# 1tm32_test.net
KiCad netlist of a schematic drawn in EAGLE
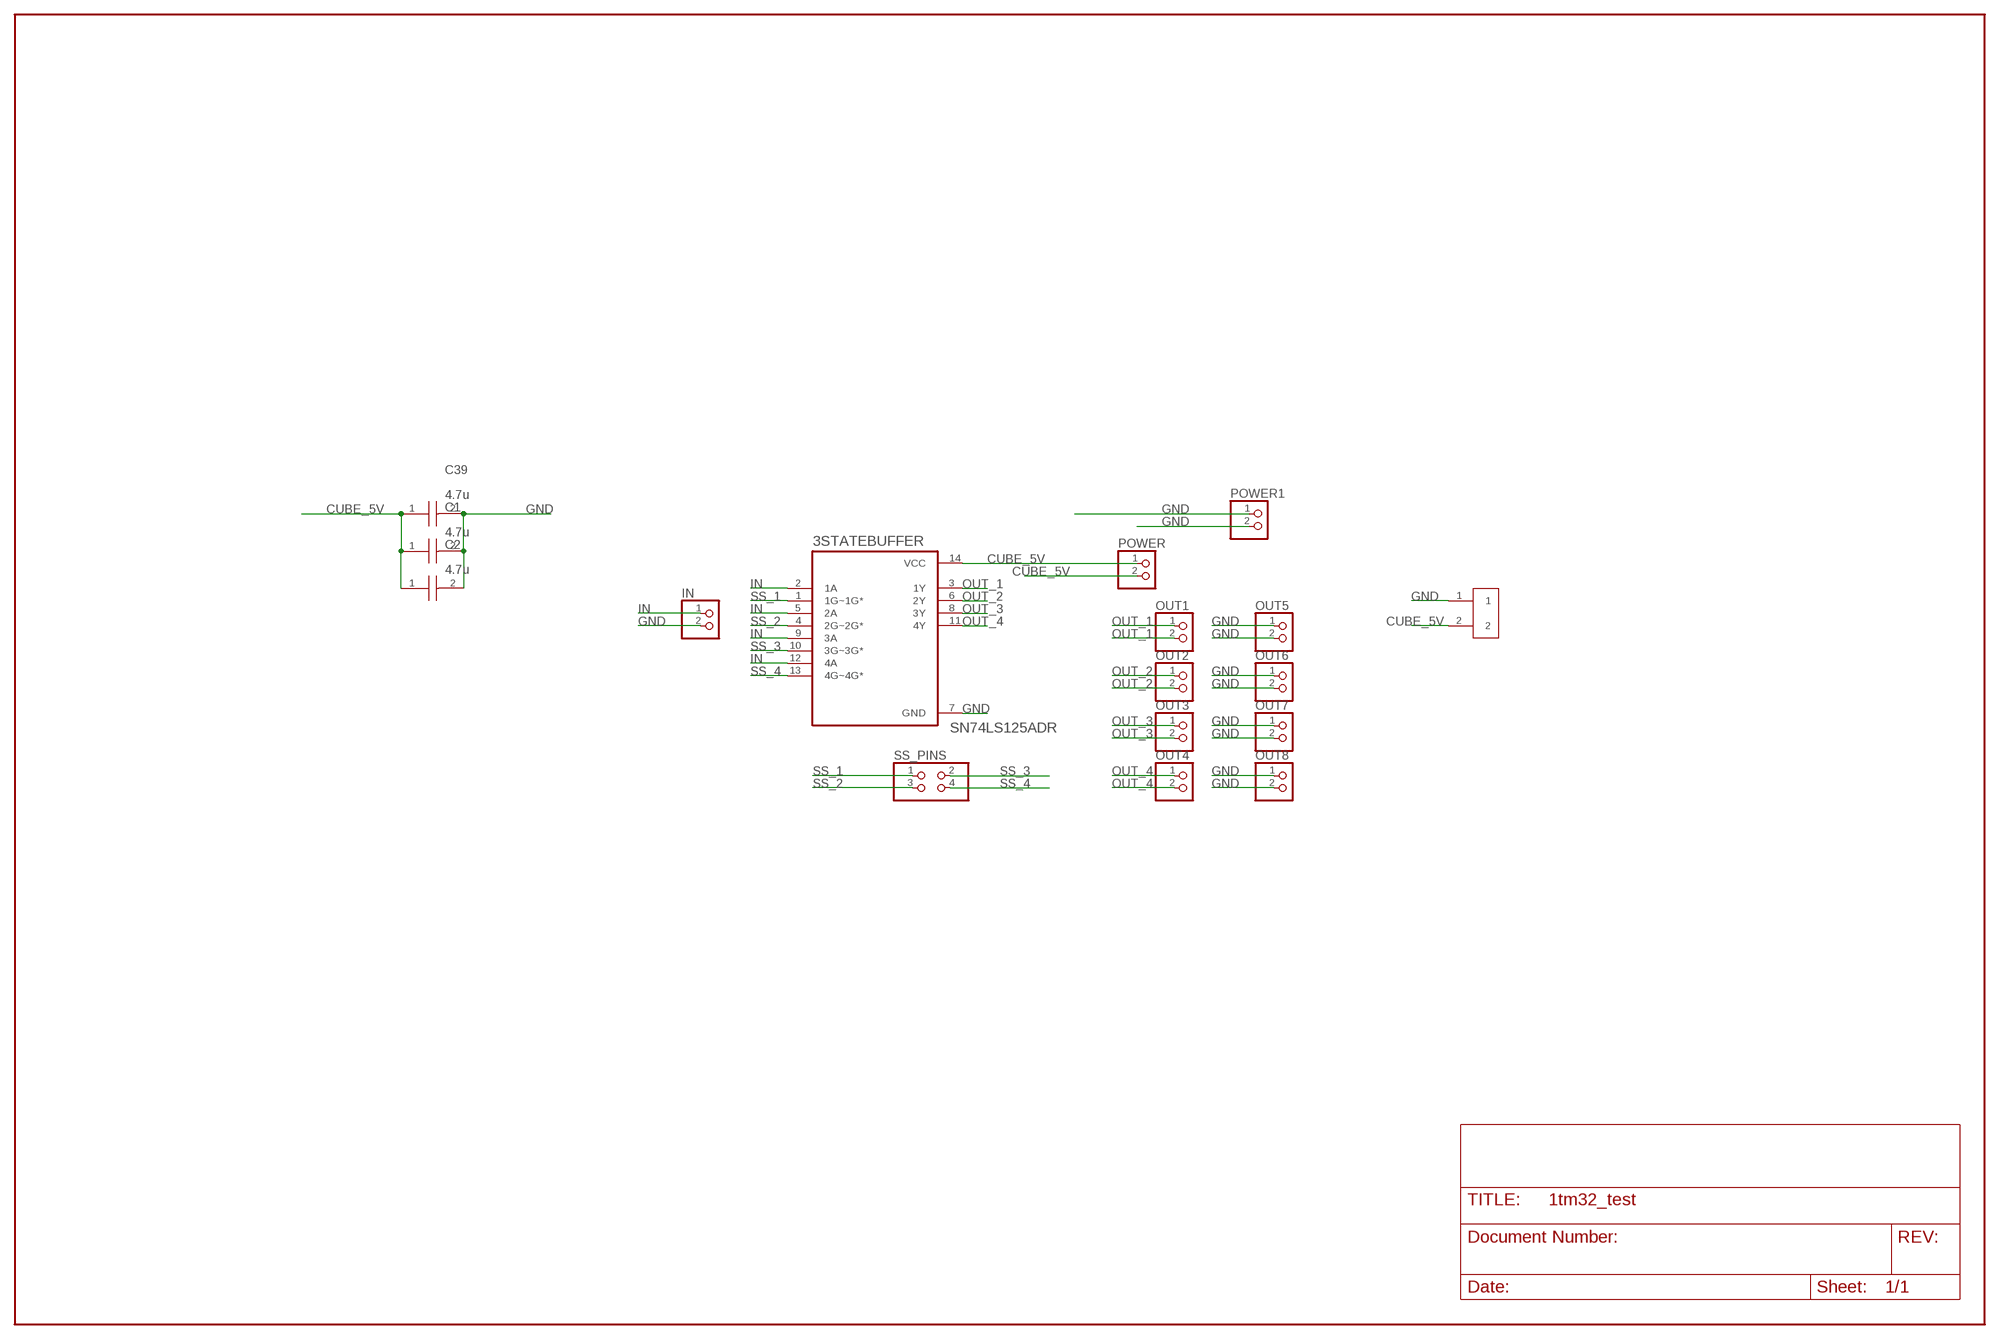
[diagram p0: schematic, sheet 1]

(export (version "E")
  (design (tool "Eeschema 10.0.6"))
  (components
    (comp (ref "3STATEBUFFER")
      (value "SN74LS125ADR")
      (footprint "eagle-import:SOIC127P600X175-14N")
      (fields (field (name "MF") "Texas Instruments"))
      (libsource (lib "eagle-import") (part "SN74LS125ADR"))
    )
    (comp (ref "C1")
      (value "4.7u")
      (footprint "eagle-import:CAPC2012X145N")
      (fields
        (field (name "MANUFACTURER_PART_NUMBER") "GRT21BC71H475KE13L")
        (field (name "MOUSER_PART_NUMBER") "81-GRT21BC71H475KE3L")
      )
      (libsource (lib "eagle-import") (part "GRT21BC71H475KE13L"))
    )
    (comp (ref "C2")
      (value "4.7u")
      (footprint "eagle-import:CAPC2012X145N")
      (fields
        (field (name "MANUFACTURER_PART_NUMBER") "GRT21BC71H475KE13L")
        (field (name "MOUSER_PART_NUMBER") "81-GRT21BC71H475KE3L")
      )
      (libsource (lib "eagle-import") (part "GRT21BC71H475KE13L"))
    )
    (comp (ref "C39")
      (value "4.7u")
      (footprint "eagle-import:CAPC2012X145N")
      (fields
        (field (name "MANUFACTURER_PART_NUMBER") "GRT21BC71H475KE13L")
        (field (name "MOUSER_PART_NUMBER") "81-GRT21BC71H475KE3L")
      )
      (libsource (lib "eagle-import") (part "GRT21BC71H475KE13L"))
    )
    (comp (ref "IN")
      (value "PINHD-1X2")
      (footprint "eagle-import:1X02")
      (libsource (lib "eagle-import") (part "PINHD-1X2"))
    )
    (comp (ref "J1")
      (value "1935161")
      (footprint "eagle-import:PHOENIX_1935161")
      (fields (field (name "MF") "Phoenix Contact"))
      (libsource (lib "eagle-import") (part "1935161"))
    )
    (comp (ref "OUT1")
      (value "PINHD-1X2")
      (footprint "eagle-import:1X02")
      (libsource (lib "eagle-import") (part "PINHD-1X2"))
    )
    (comp (ref "OUT2")
      (value "PINHD-1X2")
      (footprint "eagle-import:1X02")
      (libsource (lib "eagle-import") (part "PINHD-1X2"))
    )
    (comp (ref "OUT3")
      (value "PINHD-1X2")
      (footprint "eagle-import:1X02")
      (libsource (lib "eagle-import") (part "PINHD-1X2"))
    )
    (comp (ref "OUT4")
      (value "PINHD-1X2")
      (footprint "eagle-import:1X02")
      (libsource (lib "eagle-import") (part "PINHD-1X2"))
    )
    (comp (ref "OUT5")
      (value "PINHD-1X2")
      (footprint "eagle-import:1X02")
      (libsource (lib "eagle-import") (part "PINHD-1X2"))
    )
    (comp (ref "OUT6")
      (value "PINHD-1X2")
      (footprint "eagle-import:1X02")
      (libsource (lib "eagle-import") (part "PINHD-1X2"))
    )
    (comp (ref "OUT7")
      (value "PINHD-1X2")
      (footprint "eagle-import:1X02")
      (libsource (lib "eagle-import") (part "PINHD-1X2"))
    )
    (comp (ref "OUT8")
      (value "PINHD-1X2")
      (footprint "eagle-import:1X02")
      (libsource (lib "eagle-import") (part "PINHD-1X2"))
    )
    (comp (ref "POWER")
      (value "PINHD-1X2")
      (footprint "eagle-import:1X02")
      (libsource (lib "eagle-import") (part "PINHD-1X2"))
    )
    (comp (ref "POWER1")
      (value "PINHD-1X2")
      (footprint "eagle-import:1X02")
      (libsource (lib "eagle-import") (part "PINHD-1X2"))
    )
    (comp (ref "SS_PINS")
      (value "PINHD-2X2")
      (footprint "eagle-import:2X02")
      (libsource (lib "eagle-import") (part "PINHD-2X2"))
    )
  )
  (nets
    (net (code "1") (name "/CUBE_5V") (class "Default")
      (node (ref "3STATEBUFFER") (pin "14") (pinfunction "VCC_14") (pintype "power_in"))
      (node (ref "C1") (pin "1") (pinfunction "1_1") (pintype "bidirectional"))
      (node (ref "C2") (pin "1") (pinfunction "1_1") (pintype "bidirectional"))
      (node (ref "C39") (pin "1") (pinfunction "1_1") (pintype "bidirectional"))
      (node (ref "J1") (pin "2") (pinfunction "2_2") (pintype "passive"))
      (node (ref "POWER") (pin "1") (pinfunction "1_1") (pintype "passive"))
      (node (ref "POWER") (pin "2") (pinfunction "2_2") (pintype "passive"))
    )
    (net (code "2") (name "/GND") (class "Default")
      (node (ref "3STATEBUFFER") (pin "7") (pinfunction "GND_7") (pintype "power_in"))
      (node (ref "C1") (pin "2") (pinfunction "2_2") (pintype "bidirectional"))
      (node (ref "C2") (pin "2") (pinfunction "2_2") (pintype "bidirectional"))
      (node (ref "C39") (pin "2") (pinfunction "2_2") (pintype "bidirectional"))
      (node (ref "IN") (pin "2") (pinfunction "2_2") (pintype "passive"))
      (node (ref "J1") (pin "1") (pinfunction "1_1") (pintype "passive"))
      (node (ref "OUT5") (pin "1") (pinfunction "1_1") (pintype "passive"))
      (node (ref "OUT5") (pin "2") (pinfunction "2_2") (pintype "passive"))
      (node (ref "OUT6") (pin "1") (pinfunction "1_1") (pintype "passive"))
      (node (ref "OUT6") (pin "2") (pinfunction "2_2") (pintype "passive"))
      (node (ref "OUT7") (pin "1") (pinfunction "1_1") (pintype "passive"))
      (node (ref "OUT7") (pin "2") (pinfunction "2_2") (pintype "passive"))
      (node (ref "OUT8") (pin "1") (pinfunction "1_1") (pintype "passive"))
      (node (ref "OUT8") (pin "2") (pinfunction "2_2") (pintype "passive"))
      (node (ref "POWER1") (pin "1") (pinfunction "1_1") (pintype "passive"))
      (node (ref "POWER1") (pin "2") (pinfunction "2_2") (pintype "passive"))
    )
    (net (code "3") (name "/IN") (class "Default")
      (node (ref "3STATEBUFFER") (pin "12") (pinfunction "4A_12") (pintype "input"))
      (node (ref "3STATEBUFFER") (pin "2") (pinfunction "1A_2") (pintype "input"))
      (node (ref "3STATEBUFFER") (pin "5") (pinfunction "2A_5") (pintype "input"))
      (node (ref "3STATEBUFFER") (pin "9") (pinfunction "3A_9") (pintype "input"))
      (node (ref "IN") (pin "1") (pinfunction "1_1") (pintype "passive"))
    )
    (net (code "4") (name "/OUT_1") (class "Default")
      (node (ref "3STATEBUFFER") (pin "3") (pinfunction "1Y_3") (pintype "output"))
      (node (ref "OUT1") (pin "1") (pinfunction "1_1") (pintype "passive"))
      (node (ref "OUT1") (pin "2") (pinfunction "2_2") (pintype "passive"))
    )
    (net (code "5") (name "/OUT_2") (class "Default")
      (node (ref "3STATEBUFFER") (pin "6") (pinfunction "2Y_6") (pintype "output"))
      (node (ref "OUT2") (pin "1") (pinfunction "1_1") (pintype "passive"))
      (node (ref "OUT2") (pin "2") (pinfunction "2_2") (pintype "passive"))
    )
    (net (code "6") (name "/OUT_3") (class "Default")
      (node (ref "3STATEBUFFER") (pin "8") (pinfunction "3Y_8") (pintype "output"))
      (node (ref "OUT3") (pin "1") (pinfunction "1_1") (pintype "passive"))
      (node (ref "OUT3") (pin "2") (pinfunction "2_2") (pintype "passive"))
    )
    (net (code "7") (name "/OUT_4") (class "Default")
      (node (ref "3STATEBUFFER") (pin "11") (pinfunction "4Y_11") (pintype "output"))
      (node (ref "OUT4") (pin "1") (pinfunction "1_1") (pintype "passive"))
      (node (ref "OUT4") (pin "2") (pinfunction "2_2") (pintype "passive"))
    )
    (net (code "8") (name "/SS_1") (class "Default")
      (node (ref "3STATEBUFFER") (pin "1") (pinfunction "1G~{1G*}_1") (pintype "input"))
      (node (ref "SS_PINS") (pin "1") (pinfunction "1_1") (pintype "passive"))
    )
    (net (code "9") (name "/SS_2") (class "Default")
      (node (ref "3STATEBUFFER") (pin "4") (pinfunction "2G~{2G*}_4") (pintype "input"))
      (node (ref "SS_PINS") (pin "3") (pinfunction "3_3") (pintype "passive"))
    )
    (net (code "10") (name "/SS_3") (class "Default")
      (node (ref "3STATEBUFFER") (pin "10") (pinfunction "3G~{3G*}_10") (pintype "input"))
      (node (ref "SS_PINS") (pin "2") (pinfunction "2_2") (pintype "passive"))
    )
    (net (code "11") (name "/SS_4") (class "Default")
      (node (ref "3STATEBUFFER") (pin "13") (pinfunction "4G~{4G*}_13") (pintype "input"))
      (node (ref "SS_PINS") (pin "4") (pinfunction "4_4") (pintype "passive"))
    )
  )
)
